# Mergen_Ground_Station_V2_0.net
KiCad netlist of a schematic drawn in EAGLE
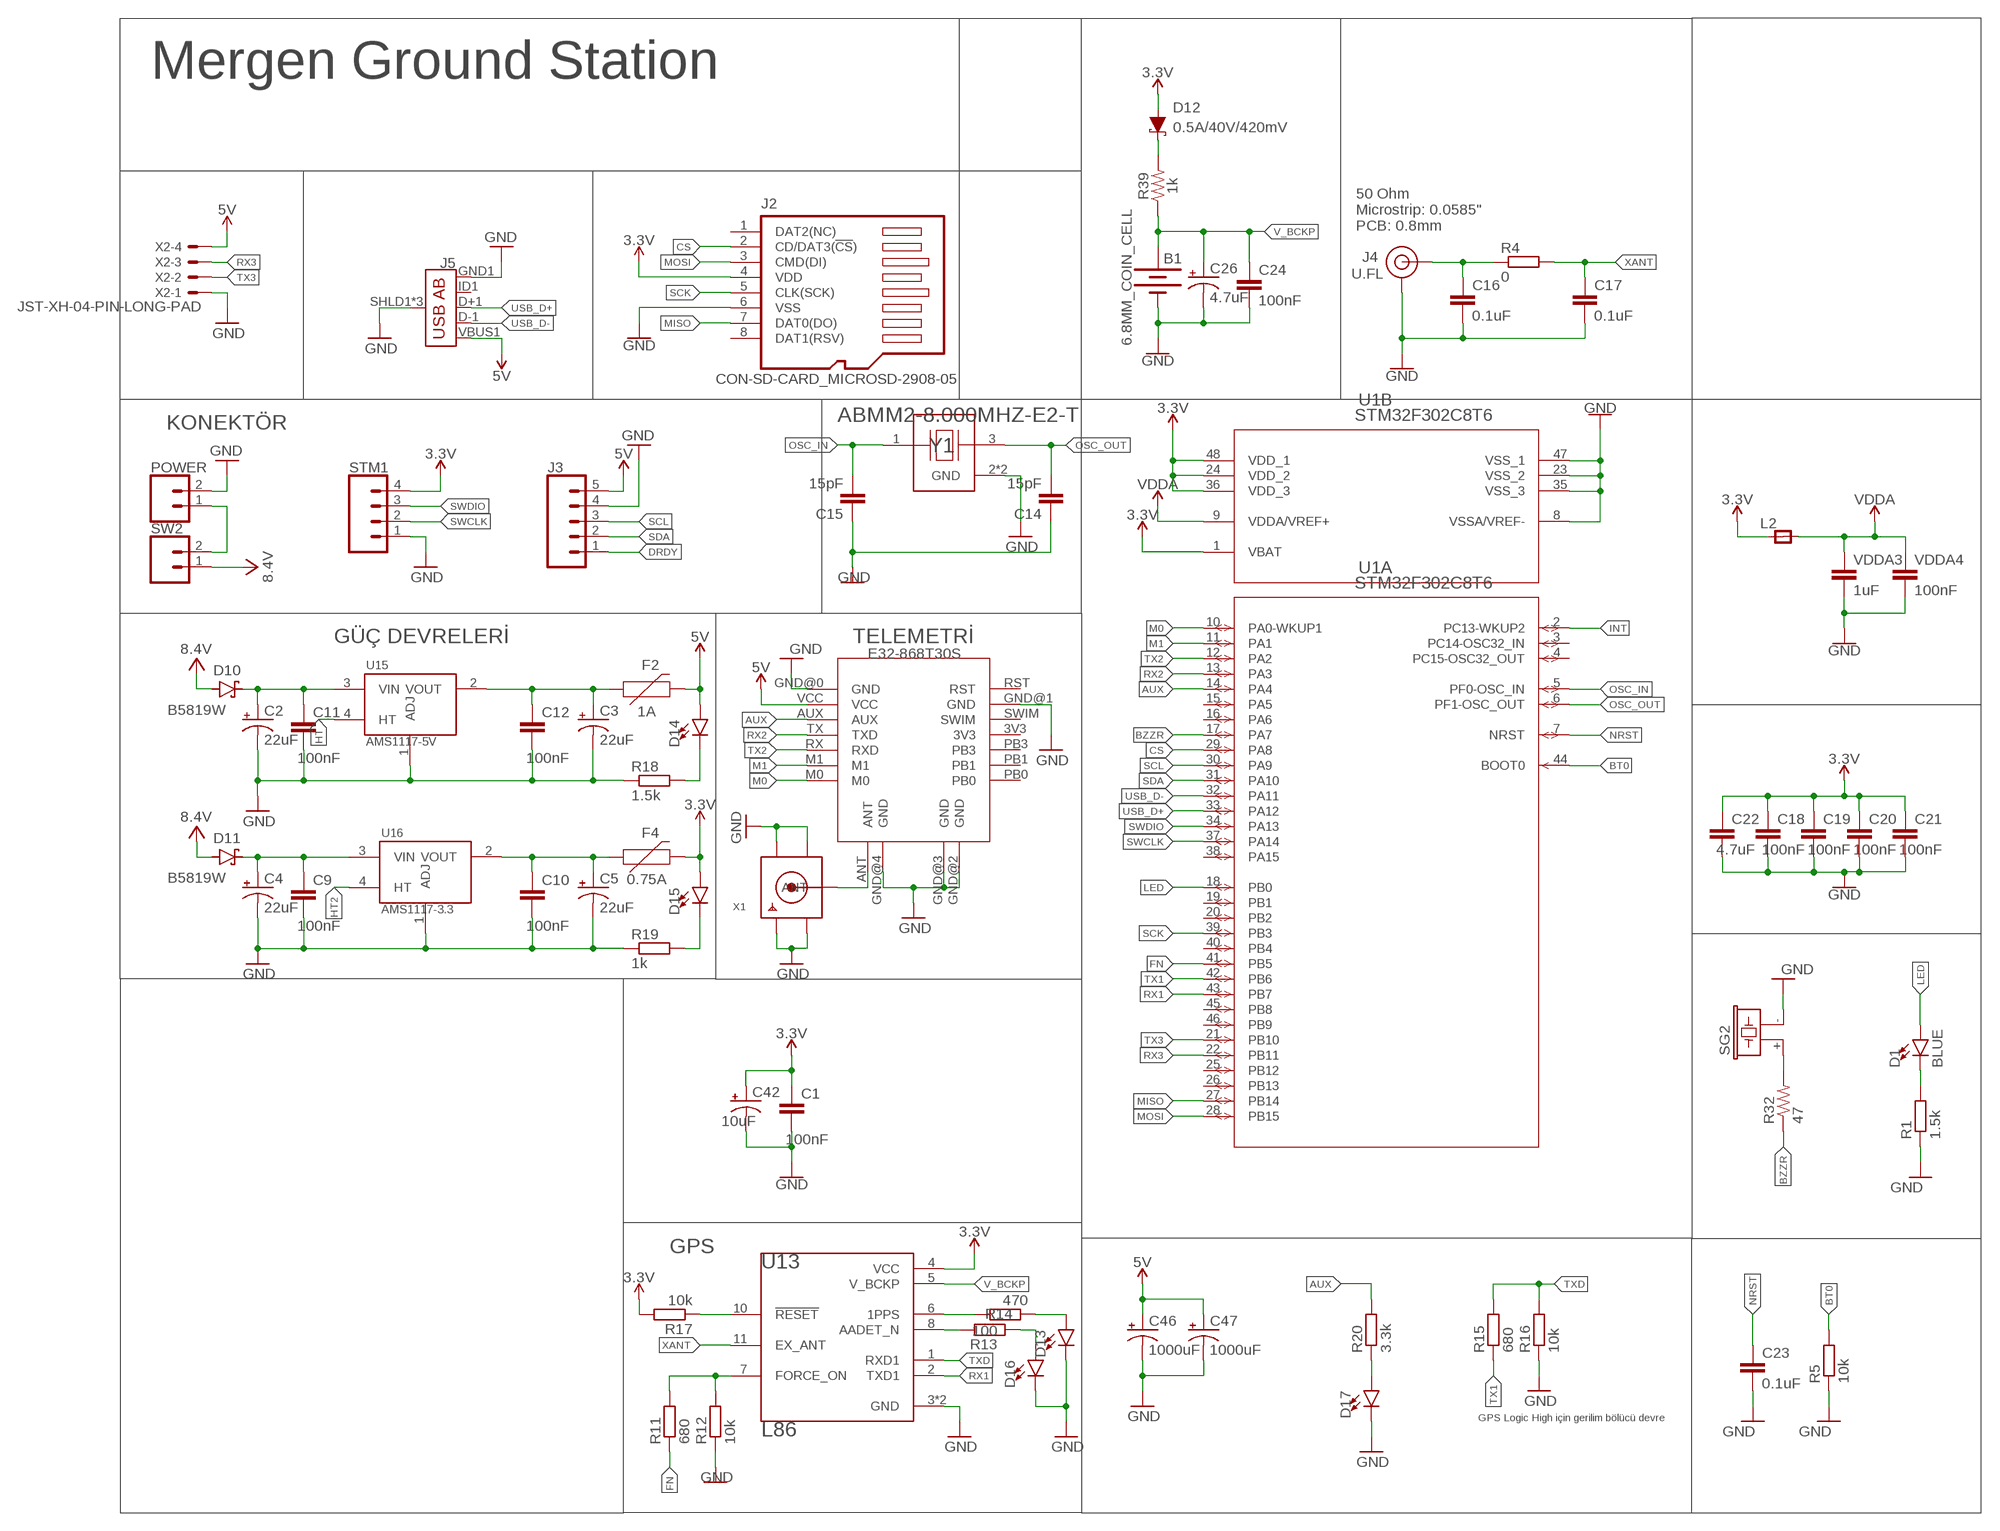
[diagram p0: schematic, sheet 1]

(export (version "E")
  (design (tool "Eeschema 10.0.6"))
  (components
    (comp (ref "B1")
      (value "6.8MM_COIN_CELL")
      (footprint "eagle-import:BATTCON-6.8MM")
      (libsource (lib "eagle-import") (part "BATTERY-6.8MM_SMD"))
    )
    (comp (ref "C1")
      (value "100nF")
      (footprint "eagle-import:C0603")
      (libsource (lib "eagle-import") (part "C-EUC0603"))
    )
    (comp (ref "C2")
      (value "22uF")
      (footprint "eagle-import:CT3528")
      (libsource (lib "eagle-import") (part "rcl_334_CPOL-USCT3528"))
    )
    (comp (ref "C3")
      (value "22uF")
      (footprint "eagle-import:CT3528")
      (libsource (lib "eagle-import") (part "rcl_334_CPOL-USCT3528"))
    )
    (comp (ref "C4")
      (value "22uF")
      (footprint "eagle-import:CT3528")
      (libsource (lib "eagle-import") (part "rcl_334_CPOL-USCT3528"))
    )
    (comp (ref "C5")
      (value "22uF")
      (footprint "eagle-import:CT3528")
      (libsource (lib "eagle-import") (part "rcl_334_CPOL-USCT3528"))
    )
    (comp (ref "C9")
      (value "100nF")
      (footprint "eagle-import:C0603")
      (libsource (lib "eagle-import") (part "C-EUC0603"))
    )
    (comp (ref "C10")
      (value "100nF")
      (footprint "eagle-import:C0603")
      (libsource (lib "eagle-import") (part "C-EUC0603"))
    )
    (comp (ref "C11")
      (value "100nF")
      (footprint "eagle-import:C0603")
      (libsource (lib "eagle-import") (part "C-EUC0603"))
    )
    (comp (ref "C12")
      (value "100nF")
      (footprint "eagle-import:C0603")
      (libsource (lib "eagle-import") (part "C-EUC0603"))
    )
    (comp (ref "C14")
      (value "15pF")
      (footprint "eagle-import:C0603")
      (libsource (lib "eagle-import") (part "C-EUC0603"))
    )
    (comp (ref "C15")
      (value "15pF")
      (footprint "eagle-import:C0603")
      (libsource (lib "eagle-import") (part "C-EUC0603"))
    )
    (comp (ref "C16")
      (value "0.1uF")
      (footprint "eagle-import:C0603")
      (libsource (lib "eagle-import") (part "C-EUC0603"))
    )
    (comp (ref "C17")
      (value "0.1uF")
      (footprint "eagle-import:C0603")
      (libsource (lib "eagle-import") (part "C-EUC0603"))
    )
    (comp (ref "C18")
      (value "100nF")
      (footprint "eagle-import:C0603")
      (libsource (lib "eagle-import") (part "C-EUC0603"))
    )
    (comp (ref "C19")
      (value "100nF")
      (footprint "eagle-import:C0603")
      (libsource (lib "eagle-import") (part "C-EUC0603"))
    )
    (comp (ref "C20")
      (value "100nF")
      (footprint "eagle-import:C0603")
      (libsource (lib "eagle-import") (part "C-EUC0603"))
    )
    (comp (ref "C21")
      (value "100nF")
      (footprint "eagle-import:C0603")
      (libsource (lib "eagle-import") (part "C-EUC0603"))
    )
    (comp (ref "C22")
      (value "4.7uF")
      (footprint "eagle-import:C0603")
      (libsource (lib "eagle-import") (part "C-EUC0603"))
    )
    (comp (ref "C23")
      (value "0.1uF")
      (footprint "eagle-import:C0603")
      (libsource (lib "eagle-import") (part "C-EUC0603"))
    )
    (comp (ref "C24")
      (value "100nF")
      (footprint "eagle-import:C0603")
      (libsource (lib "eagle-import") (part "C-EUC0603"))
    )
    (comp (ref "C26")
      (value "4.7uF")
      (footprint "eagle-import:A_3216-18R")
      (libsource (lib "eagle-import") (part "rcl_334_CPOL-USA/3216-18R"))
    )
    (comp (ref "C42")
      (value "10uF")
      (footprint "eagle-import:EIA3216")
      (libsource (lib "eagle-import") (part "10UF-POLAR-EIA3216-16V-10%(TANT)"))
    )
    (comp (ref "C46")
      (value "1000uF")
      (footprint "eagle-import:150CLZ-1010")
      (libsource (lib "eagle-import") (part "CPOL-US150CLZ-1010"))
    )
    (comp (ref "C47")
      (value "1000uF")
      (footprint "eagle-import:150CLZ-1010")
      (libsource (lib "eagle-import") (part "CPOL-US150CLZ-1010"))
    )
    (comp (ref "D1")
      (value "BLUE")
      (footprint "eagle-import:LED-0603")
      (libsource (lib "eagle-import") (part "LED0603"))
    )
    (comp (ref "D10")
      (value "B5819W")
      (footprint "eagle-import:SODFL3718X115")
      (fields (field (name "MANUFACTURER") "ON Semiconductor") (field (name "MPN") "MBR0520LT1G"))
      (libsource (lib "eagle-import") (part "SCHOTTKY_DO-219MBR0520LT1G"))
    )
    (comp (ref "D11")
      (value "B5819W")
      (footprint "eagle-import:SODFL3718X115")
      (fields (field (name "MANUFACTURER") "ON Semiconductor") (field (name "MPN") "MBR0520LT1G"))
      (libsource (lib "eagle-import") (part "SCHOTTKY_DO-219MBR0520LT1G"))
    )
    (comp (ref "D12")
      (value "0.5A/40V/420mV")
      (footprint "eagle-import:SOD-323")
      (libsource (lib "eagle-import") (part "DIODE-SCHOTTKY-PMEG4005EJ"))
    )
    (comp (ref "D13")
      (value "LED0603")
      (footprint "eagle-import:LED-0603")
      (libsource (lib "eagle-import") (part "LED0603"))
    )
    (comp (ref "D14")
      (value "LED0603")
      (footprint "eagle-import:LED-0603")
      (libsource (lib "eagle-import") (part "LED0603"))
    )
    (comp (ref "D15")
      (value "LED0603")
      (footprint "eagle-import:LED-0603")
      (libsource (lib "eagle-import") (part "LED0603"))
    )
    (comp (ref "D16")
      (value "LED0603")
      (footprint "eagle-import:LED-0603")
      (libsource (lib "eagle-import") (part "LED0603"))
    )
    (comp (ref "D17")
      (value "LED0603")
      (footprint "eagle-import:LED-0603")
      (libsource (lib "eagle-import") (part "LED0603"))
    )
    (comp (ref "F2")
      (value "1A")
      (footprint "eagle-import:1206")
      (libsource (lib "eagle-import") (part "PPTC_HALF-AMP"))
    )
    (comp (ref "F4")
      (value "0.75A")
      (footprint "eagle-import:1206")
      (libsource (lib "eagle-import") (part "PPTC_HALF-AMP"))
    )
    (comp (ref "J2")
      (value "CON-SD-CARD_MICROSD-2908-05")
      (footprint "eagle-import:CON-SD-CARD_2908-05")
      (libsource (lib "eagle-import") (part "CON-SD-CARD_MICROSD-2908-05"))
    )
    (comp (ref "J3")
      (value "CONN_05LOCK_LONGPADS")
      (footprint "eagle-import:1X05_LOCK_LONGPADS")
      (libsource (lib "eagle-import") (part "CONN_05LOCK_LONGPADS"))
    )
    (comp (ref "J4")
      (value "U.FL")
      (footprint "eagle-import:U.FL")
      (libsource (lib "eagle-import") (part "U.FL2PIN"))
    )
    (comp (ref "J5")
      (value "USB_AB_SMT")
      (footprint "eagle-import:USB-AB-MICRO-SMD")
      (libsource (lib "eagle-import") (part "USB_AB_SMT"))
    )
    (comp (ref "L2")
      (value "RC-MASTER-SMD_FB_0805MP")
      (footprint "eagle-import:RC-MASTER-SMD_L0805MP")
      (libsource (lib "eagle-import") (part "RC-MASTER-SMD_FB_0805MP"))
    )
    (comp (ref "POWER")
      (value "CONN_023.5MM-NO_SILK")
      (footprint "eagle-import:SCREWTERMINAL-3.5MM-2-NS")
      (libsource (lib "eagle-import") (part "CONN_023.5MM-NO_SILK"))
    )
    (comp (ref "R1")
      (value "1.5k")
      (footprint "eagle-import:R0603")
      (libsource (lib "eagle-import") (part "R-EU_R0603"))
    )
    (comp (ref "R4")
      (value "0")
      (footprint "eagle-import:R0603")
      (libsource (lib "eagle-import") (part "R-EU_R0603"))
    )
    (comp (ref "R5")
      (value "10k")
      (footprint "eagle-import:R0603")
      (libsource (lib "eagle-import") (part "R-EU_R0603"))
    )
    (comp (ref "R11")
      (value "680")
      (footprint "eagle-import:R0603")
      (libsource (lib "eagle-import") (part "R-EU_R0603"))
    )
    (comp (ref "R12")
      (value "10k")
      (footprint "eagle-import:R0603")
      (libsource (lib "eagle-import") (part "R-EU_R0603"))
    )
    (comp (ref "R13")
      (value "100")
      (footprint "eagle-import:R0603")
      (libsource (lib "eagle-import") (part "R-EU_R0603"))
    )
    (comp (ref "R14")
      (value "470")
      (footprint "eagle-import:R0603")
      (libsource (lib "eagle-import") (part "R-EU_R0603"))
    )
    (comp (ref "R15")
      (value "680")
      (footprint "eagle-import:R0603")
      (libsource (lib "eagle-import") (part "R-EU_R0603"))
    )
    (comp (ref "R16")
      (value "10k")
      (footprint "eagle-import:R0603")
      (libsource (lib "eagle-import") (part "R-EU_R0603"))
    )
    (comp (ref "R17")
      (value "10k")
      (footprint "eagle-import:R0603")
      (libsource (lib "eagle-import") (part "R-EU_R0603"))
    )
    (comp (ref "R18")
      (value "1.5k")
      (footprint "eagle-import:R0603")
      (libsource (lib "eagle-import") (part "R-EU_R0603"))
    )
    (comp (ref "R19")
      (value "1k")
      (footprint "eagle-import:R0603")
      (libsource (lib "eagle-import") (part "R-EU_R0603"))
    )
    (comp (ref "R20")
      (value "3.3k")
      (footprint "eagle-import:R0603")
      (libsource (lib "eagle-import") (part "R-EU_R0603"))
    )
    (comp (ref "R32")
      (value "47")
      (footprint "eagle-import:0603")
      (libsource (lib "eagle-import") (part "0OHM-0603-1/10W-5%"))
    )
    (comp (ref "R39")
      (value "1k")
      (footprint "eagle-import:0603")
      (libsource (lib "eagle-import") (part "1KOHM-0603-1/10W-1%"))
    )
    (comp (ref "SG2")
      (value "F/CM12P")
      (footprint "eagle-import:F_CM12P")
      (libsource (lib "eagle-import") (part "F/CM12P"))
    )
    (comp (ref "STM1")
      (value "CONN_04")
      (footprint "eagle-import:1X04")
      (libsource (lib "eagle-import") (part "CONN_04"))
    )
    (comp (ref "SW2")
      (value "CONN_023.5MM-NO_SILK")
      (footprint "eagle-import:SCREWTERMINAL-3.5MM-2-NS")
      (libsource (lib "eagle-import") (part "CONN_023.5MM-NO_SILK"))
    )
    (comp (ref "U1")
      (value "STM32F302C8T6")
      (footprint "eagle-import:LQFP48-7X7MM")
      (fields (field (name "COPYRIGHT") "Copyright (C) 2018 Accelerated Designs. All rights reserved"))
      (libsource (lib "eagle-import") (part "STM32F302C8T6"))
    )
    (comp (ref "U13")
      (value "L86")
      (footprint "eagle-import:XCVR_L86")
      (fields (field (name "MF") "Quectel"))
      (libsource (lib "eagle-import") (part "L86"))
    )
    (comp (ref "U14")
      (value "E32-868T30S")
      (footprint "eagle-import:E32-868T30S")
      (libsource (lib "eagle-import") (part "E32-868T30S"))
    )
    (comp (ref "U15")
      (value "AMS1117-5V")
      (footprint "eagle-import:SOT229P700X180-4N")
      (fields (field (name "MF") "Advanced Monolithic Systems") (field (name "MP") "AMS1117-3.3"))
      (libsource (lib "eagle-import") (part "AMS1117-3.3"))
    )
    (comp (ref "U16")
      (value "AMS1117-3.3")
      (footprint "eagle-import:SOT229P700X180-4N")
      (fields (field (name "MF") "Advanced Monolithic Systems"))
      (libsource (lib "eagle-import") (part "AMS1117-3.3"))
    )
    (comp (ref "VDDA3")
      (value "1uF")
      (footprint "eagle-import:0603")
      (libsource (lib "eagle-import") (part "0.1UF-0603-25V-(+80/-20%)"))
    )
    (comp (ref "VDDA4")
      (value "100nF")
      (footprint "eagle-import:0603")
      (libsource (lib "eagle-import") (part "0.1UF-0603-25V-(+80/-20%)"))
    )
    (comp (ref "X1")
      (value "SMACONNECTOR")
      (footprint "eagle-import:SMA90_DIP")
      (libsource (lib "eagle-import") (part "SMACONNECTOR"))
    )
    (comp (ref "X2")
      (value "JST-XH-04-PIN-LONG-PAD")
      (footprint "eagle-import:JST-XH-04-PACKAGE-LONG-PAD")
      (libsource (lib "eagle-import") (part "JST-XH-04-PIN-LONG-PAD"))
    )
    (comp (ref "Y1")
      (value "ABMM2-8.000MHZ-E2-T")
      (footprint "eagle-import:XTAL_ABMM2-8.000MHZ-E2-T")
      (fields (field (name "MF") "Abracon"))
      (libsource (lib "eagle-import") (part "ABMM2-8.000MHZ-E2-T"))
    )
  )
  (nets
    (net (code "1") (name "3.3V") (class "Default")
      (node (ref "C1") (pin "1") (pinfunction "1_1") (pintype "passive"))
      (node (ref "C18") (pin "1") (pinfunction "1_1") (pintype "passive"))
      (node (ref "C19") (pin "1") (pinfunction "1_1") (pintype "passive"))
      (node (ref "C20") (pin "1") (pinfunction "1_1") (pintype "passive"))
      (node (ref "C21") (pin "1") (pinfunction "1_1") (pintype "passive"))
      (node (ref "C22") (pin "1") (pinfunction "1_1") (pintype "passive"))
      (node (ref "C42") (pin "+") (pinfunction "+_+") (pintype "passive"))
      (node (ref "D12") (pin "A") (pinfunction "A_A") (pintype "passive"))
      (node (ref "D15") (pin "A") (pinfunction "A_A") (pintype "passive"))
      (node (ref "F4") (pin "2") (pinfunction "2_2") (pintype "bidirectional"))
      (node (ref "J2") (pin "4") (pinfunction "VDD_4") (pintype "bidirectional"))
      (node (ref "L2") (pin "1") (pinfunction "1_1") (pintype "passive"))
      (node (ref "R17") (pin "2") (pinfunction "2_2") (pintype "passive"))
      (node (ref "STM1") (pin "4") (pinfunction "4_4") (pintype "passive"))
      (node (ref "U1") (pin "1") (pinfunction "VBAT_1") (pintype "power_in"))
      (node (ref "U1") (pin "24") (pinfunction "VDD_2_24") (pintype "power_in"))
      (node (ref "U1") (pin "36") (pinfunction "VDD_3_36") (pintype "power_in"))
      (node (ref "U1") (pin "48") (pinfunction "VDD_1_48") (pintype "power_in"))
      (node (ref "U13") (pin "4") (pinfunction "VCC_4") (pintype "power_in"))
    )
    (net (code "2") (name "5V") (class "Default")
      (node (ref "C46") (pin "+") (pinfunction "+_+") (pintype "passive"))
      (node (ref "C47") (pin "+") (pinfunction "+_+") (pintype "passive"))
      (node (ref "D14") (pin "A") (pinfunction "A_A") (pintype "passive"))
      (node (ref "F2") (pin "2") (pinfunction "2_2") (pintype "bidirectional"))
      (node (ref "J3") (pin "5") (pinfunction "5_5") (pintype "passive"))
      (node (ref "J5") (pin "VBUS1") (pinfunction "VBUS_VBUS1") (pintype "power_in"))
      (node (ref "U14") (pin "VCC") (pinfunction "VCC_VCC") (pintype "bidirectional"))
      (node (ref "X2") (pin "4") (pinfunction "S_4") (pintype "passive"))
    )
    (net (code "3") (name "8.4V") (class "Default")
      (node (ref "D10") (pin "2") (pinfunction "A_2") (pintype "passive"))
      (node (ref "D11") (pin "2") (pinfunction "A_2") (pintype "passive"))
      (node (ref "SW2") (pin "1") (pinfunction "1_1") (pintype "passive"))
    )
    (net (code "4") (name "AUX") (class "Default")
      (node (ref "R20") (pin "2") (pinfunction "2_2") (pintype "passive"))
      (node (ref "U1") (pin "14") (pinfunction "PA4_14") (pintype "bidirectional"))
      (node (ref "U14") (pin "AUX") (pinfunction "AUX_AUX") (pintype "bidirectional"))
    )
    (net (code "5") (name "BT0") (class "Default")
      (node (ref "R5") (pin "2") (pinfunction "2_2") (pintype "passive"))
      (node (ref "U1") (pin "44") (pinfunction "BOOT0_44") (pintype "input"))
    )
    (net (code "6") (name "BZZR") (class "Default")
      (node (ref "R32") (pin "1") (pinfunction "1_1") (pintype "passive"))
      (node (ref "U1") (pin "17") (pinfunction "PA7_17") (pintype "bidirectional"))
    )
    (net (code "7") (name "CS") (class "Default")
      (node (ref "J2") (pin "2") (pinfunction "CD/DAT3(~{CS})_2") (pintype "bidirectional"))
      (node (ref "U1") (pin "29") (pinfunction "PA8_29") (pintype "bidirectional"))
    )
    (net (code "8") (name "DRDY") (class "Default")
      (node (ref "J3") (pin "1") (pinfunction "1_1") (pintype "passive"))
    )
    (net (code "9") (name "FN") (class "Default")
      (node (ref "R11") (pin "1") (pinfunction "1_1") (pintype "passive"))
      (node (ref "U1") (pin "41") (pinfunction "PB5_41") (pintype "bidirectional"))
    )
    (net (code "10") (name "GND") (class "Default")
      (node (ref "B1") (pin "-") (pinfunction "-_-") (pintype "power_in"))
      (node (ref "C1") (pin "2") (pinfunction "2_2") (pintype "passive"))
      (node (ref "C10") (pin "2") (pinfunction "2_2") (pintype "passive"))
      (node (ref "C11") (pin "2") (pinfunction "2_2") (pintype "passive"))
      (node (ref "C12") (pin "2") (pinfunction "2_2") (pintype "passive"))
      (node (ref "C14") (pin "1") (pinfunction "1_1") (pintype "passive"))
      (node (ref "C15") (pin "1") (pinfunction "1_1") (pintype "passive"))
      (node (ref "C16") (pin "2") (pinfunction "2_2") (pintype "passive"))
      (node (ref "C17") (pin "2") (pinfunction "2_2") (pintype "passive"))
      (node (ref "C18") (pin "2") (pinfunction "2_2") (pintype "passive"))
      (node (ref "C19") (pin "2") (pinfunction "2_2") (pintype "passive"))
      (node (ref "C2") (pin "-") (pinfunction "-_-") (pintype "passive"))
      (node (ref "C20") (pin "2") (pinfunction "2_2") (pintype "passive"))
      (node (ref "C21") (pin "2") (pinfunction "2_2") (pintype "passive"))
      (node (ref "C22") (pin "2") (pinfunction "2_2") (pintype "passive"))
      (node (ref "C23") (pin "2") (pinfunction "2_2") (pintype "passive"))
      (node (ref "C24") (pin "2") (pinfunction "2_2") (pintype "passive"))
      (node (ref "C26") (pin "-") (pinfunction "-_-") (pintype "passive"))
      (node (ref "C3") (pin "-") (pinfunction "-_-") (pintype "passive"))
      (node (ref "C4") (pin "-") (pinfunction "-_-") (pintype "passive"))
      (node (ref "C42") (pin "-") (pinfunction "-_-") (pintype "passive"))
      (node (ref "C46") (pin "-") (pinfunction "-_-") (pintype "passive"))
      (node (ref "C47") (pin "-") (pinfunction "-_-") (pintype "passive"))
      (node (ref "C5") (pin "-") (pinfunction "-_-") (pintype "passive"))
      (node (ref "C9") (pin "2") (pinfunction "2_2") (pintype "passive"))
      (node (ref "D13") (pin "C") (pinfunction "C_C") (pintype "passive"))
      (node (ref "D16") (pin "C") (pinfunction "C_C") (pintype "passive"))
      (node (ref "D17") (pin "C") (pinfunction "C_C") (pintype "passive"))
      (node (ref "J2") (pin "6") (pinfunction "VSS_6") (pintype "bidirectional"))
      (node (ref "J3") (pin "4") (pinfunction "4_4") (pintype "passive"))
      (node (ref "J4") (pin "1") (pinfunction "GND_1") (pintype "bidirectional"))
      (node (ref "J4") (pin "2") (pinfunction "GND_2") (pintype "bidirectional"))
      (node (ref "J5") (pin "GND1") (pinfunction "GND_GND1") (pintype "power_in"))
      (node (ref "J5") (pin "SHLD1") (pinfunction "SHIELD_SHLD1") (pintype "bidirectional"))
      (node (ref "J5") (pin "SHLD2") (pinfunction "SHIELD_SHLD2") (pintype "bidirectional"))
      (node (ref "J5") (pin "SHLD3") (pinfunction "SHIELD_SHLD3") (pintype "bidirectional"))
      (node (ref "POWER") (pin "2") (pinfunction "2_2") (pintype "passive"))
      (node (ref "R1") (pin "1") (pinfunction "1_1") (pintype "passive"))
      (node (ref "R12") (pin "1") (pinfunction "1_1") (pintype "passive"))
      (node (ref "R16") (pin "1") (pinfunction "1_1") (pintype "passive"))
      (node (ref "R18") (pin "1") (pinfunction "1_1") (pintype "passive"))
      (node (ref "R19") (pin "1") (pinfunction "1_1") (pintype "passive"))
      (node (ref "R5") (pin "1") (pinfunction "1_1") (pintype "passive"))
      (node (ref "SG2") (pin "-") (pinfunction "2_-") (pintype "passive"))
      (node (ref "STM1") (pin "1") (pinfunction "1_1") (pintype "passive"))
      (node (ref "U1") (pin "23") (pinfunction "VSS_2_23") (pintype "power_in"))
      (node (ref "U1") (pin "35") (pinfunction "VSS_3_35") (pintype "power_in"))
      (node (ref "U1") (pin "47") (pinfunction "VSS_1_47") (pintype "power_in"))
      (node (ref "U1") (pin "8") (pinfunction "VSSA/VREF-_8") (pintype "power_in"))
      (node (ref "U13") (pin "12") (pinfunction "GND_12") (pintype "passive"))
      (node (ref "U13") (pin "3") (pinfunction "GND_3") (pintype "passive"))
      (node (ref "U14") (pin "GND@0") (pinfunction "GND_GND@0") (pintype "bidirectional"))
      (node (ref "U14") (pin "GND@1") (pinfunction "GND_GND@1") (pintype "bidirectional"))
      (node (ref "U14") (pin "GND@2") (pinfunction "GND_GND@2") (pintype "bidirectional"))
      (node (ref "U14") (pin "GND@3") (pinfunction "GND_GND@3") (pintype "bidirectional"))
      (node (ref "U14") (pin "GND@4") (pinfunction "GND_GND@4") (pintype "bidirectional"))
      (node (ref "U15") (pin "1") (pinfunction "ADJ_1") (pintype "power_in"))
      (node (ref "U16") (pin "1") (pinfunction "ADJ_1") (pintype "power_in"))
      (node (ref "VDDA3") (pin "2") (pinfunction "2_2") (pintype "passive"))
      (node (ref "VDDA4") (pin "2") (pinfunction "2_2") (pintype "passive"))
      (node (ref "X1") (pin "GND1") (pinfunction "GND1_GND1") (pintype "power_in"))
      (node (ref "X1") (pin "GND2") (pinfunction "GND2_GND2") (pintype "power_in"))
      (node (ref "X1") (pin "GND3") (pinfunction "GND3_GND3") (pintype "power_in"))
      (node (ref "X1") (pin "GND4") (pinfunction "GND4_GND4") (pintype "power_in"))
      (node (ref "X2") (pin "1") (pinfunction "S_1") (pintype "passive"))
      (node (ref "Y1") (pin "2") (pinfunction "GND_2") (pintype "power_in"))
      (node (ref "Y1") (pin "4") (pinfunction "GND_4") (pintype "power_in"))
    )
    (net (code "11") (name "HT") (class "Default")
      (node (ref "U15") (pin "4") (pinfunction "HT_4") (pintype "bidirectional"))
    )
    (net (code "12") (name "HT2") (class "Default")
      (node (ref "U16") (pin "4") (pinfunction "HT_4") (pintype "bidirectional"))
    )
    (net (code "13") (name "INT") (class "Default")
      (node (ref "U1") (pin "2") (pinfunction "PC13-WKUP2_2") (pintype "bidirectional"))
    )
    (net (code "14") (name "LED") (class "Default")
      (node (ref "D1") (pin "A") (pinfunction "A_A") (pintype "passive"))
      (node (ref "U1") (pin "18") (pinfunction "PB0_18") (pintype "bidirectional"))
    )
    (net (code "15") (name "M0") (class "Default")
      (node (ref "U1") (pin "10") (pinfunction "PA0-WKUP1_10") (pintype "bidirectional"))
      (node (ref "U14") (pin "M0") (pinfunction "M0_M0") (pintype "bidirectional"))
    )
    (net (code "16") (name "M1") (class "Default")
      (node (ref "U1") (pin "11") (pinfunction "PA1_11") (pintype "bidirectional"))
      (node (ref "U14") (pin "M1") (pinfunction "M1_M1") (pintype "bidirectional"))
    )
    (net (code "17") (name "MISO") (class "Default")
      (node (ref "J2") (pin "7") (pinfunction "DAT0(DO)_7") (pintype "bidirectional"))
      (node (ref "U1") (pin "27") (pinfunction "PB14_27") (pintype "bidirectional"))
    )
    (net (code "18") (name "MOSI") (class "Default")
      (node (ref "J2") (pin "3") (pinfunction "CMD(DI)_3") (pintype "bidirectional"))
      (node (ref "U1") (pin "28") (pinfunction "PB15_28") (pintype "bidirectional"))
    )
    (net (code "19") (name "NRST") (class "Default")
      (node (ref "C23") (pin "1") (pinfunction "1_1") (pintype "passive"))
      (node (ref "U1") (pin "7") (pinfunction "NRST_7") (pintype "bidirectional"))
    )
    (net (code "20") (name "Net-(D1-PadC)") (class "Default")
      (node (ref "D1") (pin "C") (pinfunction "C_C") (pintype "passive"))
      (node (ref "R1") (pin "2") (pinfunction "2_2") (pintype "passive"))
    )
    (net (code "21") (name "Net-(D10-C)") (class "Default")
      (node (ref "C11") (pin "1") (pinfunction "1_1") (pintype "passive"))
      (node (ref "C2") (pin "+") (pinfunction "+_+") (pintype "passive"))
      (node (ref "D10") (pin "1") (pinfunction "C_1") (pintype "passive"))
      (node (ref "U15") (pin "3") (pinfunction "VIN_3") (pintype "input"))
    )
    (net (code "22") (name "Net-(D11-C)") (class "Default")
      (node (ref "C4") (pin "+") (pinfunction "+_+") (pintype "passive"))
      (node (ref "C9") (pin "1") (pinfunction "1_1") (pintype "passive"))
      (node (ref "D11") (pin "1") (pinfunction "C_1") (pintype "passive"))
      (node (ref "U16") (pin "3") (pinfunction "VIN_3") (pintype "input"))
    )
    (net (code "23") (name "Net-(D12-PadC)") (class "Default")
      (node (ref "D12") (pin "C") (pinfunction "C_C") (pintype "passive"))
      (node (ref "R39") (pin "2") (pinfunction "2_2") (pintype "passive"))
    )
    (net (code "24") (name "Net-(D13-PadA)") (class "Default")
      (node (ref "D13") (pin "A") (pinfunction "A_A") (pintype "passive"))
      (node (ref "R14") (pin "1") (pinfunction "1_1") (pintype "passive"))
    )
    (net (code "25") (name "Net-(D14-PadC)") (class "Default")
      (node (ref "D14") (pin "C") (pinfunction "C_C") (pintype "passive"))
      (node (ref "R18") (pin "2") (pinfunction "2_2") (pintype "passive"))
    )
    (net (code "26") (name "Net-(D15-PadC)") (class "Default")
      (node (ref "D15") (pin "C") (pinfunction "C_C") (pintype "passive"))
      (node (ref "R19") (pin "2") (pinfunction "2_2") (pintype "passive"))
    )
    (net (code "27") (name "Net-(D16-PadA)") (class "Default")
      (node (ref "D16") (pin "A") (pinfunction "A_A") (pintype "passive"))
      (node (ref "R13") (pin "1") (pinfunction "1_1") (pintype "passive"))
    )
    (net (code "28") (name "Net-(D17-PadA)") (class "Default")
      (node (ref "D17") (pin "A") (pinfunction "A_A") (pintype "passive"))
      (node (ref "R20") (pin "1") (pinfunction "1_1") (pintype "passive"))
    )
    (net (code "29") (name "Net-(J4-SIGNAL)") (class "Default")
      (node (ref "C16") (pin "1") (pinfunction "1_1") (pintype "passive"))
      (node (ref "J4") (pin "FEED") (pinfunction "SIGNAL_FEED") (pintype "bidirectional"))
      (node (ref "R4") (pin "1") (pinfunction "1_1") (pintype "passive"))
    )
    (net (code "30") (name "Net-(POWER-Pad1)") (class "Default")
      (node (ref "POWER") (pin "1") (pinfunction "1_1") (pintype "passive"))
      (node (ref "SW2") (pin "2") (pinfunction "2_2") (pintype "passive"))
    )
    (net (code "31") (name "Net-(SG2-1)") (class "Default")
      (node (ref "R32") (pin "2") (pinfunction "2_2") (pintype "passive"))
      (node (ref "SG2") (pin "+") (pinfunction "1_+") (pintype "passive"))
    )
    (net (code "32") (name "Net-(U13-1PPS)") (class "Default")
      (node (ref "R14") (pin "2") (pinfunction "2_2") (pintype "passive"))
      (node (ref "U13") (pin "6") (pinfunction "1PPS_6") (pintype "output"))
    )
    (net (code "33") (name "Net-(U13-AADET_N)") (class "Default")
      (node (ref "R13") (pin "2") (pinfunction "2_2") (pintype "passive"))
      (node (ref "U13") (pin "8") (pinfunction "AADET_N_8") (pintype "output"))
    )
    (net (code "34") (name "Net-(U13-FORCE_ON)") (class "Default")
      (node (ref "R11") (pin "2") (pinfunction "2_2") (pintype "passive"))
      (node (ref "R12") (pin "2") (pinfunction "2_2") (pintype "passive"))
      (node (ref "U13") (pin "7") (pinfunction "FORCE_ON_7") (pintype "input"))
    )
    (net (code "35") (name "Net-(U13-~{RESET})") (class "Default")
      (node (ref "R17") (pin "1") (pinfunction "1_1") (pintype "passive"))
      (node (ref "U13") (pin "10") (pinfunction "~{RESET}_10") (pintype "input"))
    )
    (net (code "36") (name "Net-(U15-VOUT)") (class "Default")
      (node (ref "C12") (pin "1") (pinfunction "1_1") (pintype "passive"))
      (node (ref "C3") (pin "+") (pinfunction "+_+") (pintype "passive"))
      (node (ref "F2") (pin "1") (pinfunction "1_1") (pintype "bidirectional"))
      (node (ref "U15") (pin "2") (pinfunction "VOUT_2") (pintype "output"))
    )
    (net (code "37") (name "Net-(U16-VOUT)") (class "Default")
      (node (ref "C10") (pin "1") (pinfunction "1_1") (pintype "passive"))
      (node (ref "C5") (pin "+") (pinfunction "+_+") (pintype "passive"))
      (node (ref "F4") (pin "1") (pinfunction "1_1") (pintype "bidirectional"))
      (node (ref "U16") (pin "2") (pinfunction "VOUT_2") (pintype "output"))
    )
    (net (code "38") (name "Net-(X1-ANT)") (class "Default")
      (node (ref "U14") (pin "ANT") (pinfunction "ANT_ANT") (pintype "bidirectional"))
      (node (ref "X1") (pin "ANTENNA") (pinfunction "ANT_ANTENNA") (pintype "bidirectional"))
    )
    (net (code "39") (name "OSC_IN") (class "Default")
      (node (ref "C15") (pin "2") (pinfunction "2_2") (pintype "passive"))
      (node (ref "U1") (pin "5") (pinfunction "PF0-OSC_IN_5") (pintype "bidirectional"))
      (node (ref "Y1") (pin "1") (pinfunction "1_1") (pintype "passive"))
    )
    (net (code "40") (name "OSC_OUT") (class "Default")
      (node (ref "C14") (pin "2") (pinfunction "2_2") (pintype "passive"))
      (node (ref "U1") (pin "6") (pinfunction "PF1-OSC_OUT_6") (pintype "bidirectional"))
      (node (ref "Y1") (pin "3") (pinfunction "3_3") (pintype "passive"))
    )
    (net (code "41") (name "RX1") (class "Default")
      (node (ref "U1") (pin "43") (pinfunction "PB7_43") (pintype "bidirectional"))
      (node (ref "U13") (pin "2") (pinfunction "TXD1_2") (pintype "output"))
    )
    (net (code "42") (name "RX2") (class "Default")
      (node (ref "U1") (pin "13") (pinfunction "PA3_13") (pintype "bidirectional"))
      (node (ref "U14") (pin "TX") (pinfunction "TXD_TX") (pintype "bidirectional"))
    )
    (net (code "43") (name "RX3") (class "Default")
      (node (ref "U1") (pin "22") (pinfunction "PB11_22") (pintype "bidirectional"))
      (node (ref "X2") (pin "3") (pinfunction "S_3") (pintype "passive"))
    )
    (net (code "44") (name "SCK") (class "Default")
      (node (ref "J2") (pin "5") (pinfunction "CLK(SCK)_5") (pintype "bidirectional"))
      (node (ref "U1") (pin "39") (pinfunction "PB3_39") (pintype "bidirectional"))
    )
    (net (code "45") (name "SCL") (class "Default")
      (node (ref "J3") (pin "3") (pinfunction "3_3") (pintype "passive"))
      (node (ref "U1") (pin "30") (pinfunction "PA9_30") (pintype "bidirectional"))
    )
    (net (code "46") (name "SDA") (class "Default")
      (node (ref "J3") (pin "2") (pinfunction "2_2") (pintype "passive"))
      (node (ref "U1") (pin "31") (pinfunction "PA10_31") (pintype "bidirectional"))
    )
    (net (code "47") (name "SWCLK") (class "Default")
      (node (ref "STM1") (pin "2") (pinfunction "2_2") (pintype "passive"))
      (node (ref "U1") (pin "37") (pinfunction "PA14_37") (pintype "bidirectional"))
    )
    (net (code "48") (name "SWDIO") (class "Default")
      (node (ref "STM1") (pin "3") (pinfunction "3_3") (pintype "passive"))
      (node (ref "U1") (pin "34") (pinfunction "PA13_34") (pintype "bidirectional"))
    )
    (net (code "49") (name "TX1") (class "Default")
      (node (ref "R15") (pin "1") (pinfunction "1_1") (pintype "passive"))
      (node (ref "U1") (pin "42") (pinfunction "PB6_42") (pintype "bidirectional"))
    )
    (net (code "50") (name "TX2") (class "Default")
      (node (ref "U1") (pin "12") (pinfunction "PA2_12") (pintype "bidirectional"))
      (node (ref "U14") (pin "RX") (pinfunction "RXD_RX") (pintype "bidirectional"))
    )
    (net (code "51") (name "TX3") (class "Default")
      (node (ref "U1") (pin "21") (pinfunction "PB10_21") (pintype "bidirectional"))
      (node (ref "X2") (pin "2") (pinfunction "S_2") (pintype "passive"))
    )
    (net (code "52") (name "TXD") (class "Default")
      (node (ref "R15") (pin "2") (pinfunction "2_2") (pintype "passive"))
      (node (ref "R16") (pin "2") (pinfunction "2_2") (pintype "passive"))
      (node (ref "U13") (pin "1") (pinfunction "RXD1_1") (pintype "input"))
    )
    (net (code "53") (name "USB_D+") (class "Default")
      (node (ref "J5") (pin "D+1") (pinfunction "D+_D+1") (pintype "bidirectional"))
      (node (ref "U1") (pin "33") (pinfunction "PA12_33") (pintype "bidirectional"))
    )
    (net (code "54") (name "USB_D-") (class "Default")
      (node (ref "J5") (pin "D-1") (pinfunction "D-_D-1") (pintype "bidirectional"))
      (node (ref "U1") (pin "32") (pinfunction "PA11_32") (pintype "bidirectional"))
    )
    (net (code "55") (name "VDDA") (class "Default")
      (node (ref "L2") (pin "2") (pinfunction "2_2") (pintype "passive"))
      (node (ref "U1") (pin "9") (pinfunction "VDDA/VREF+_9") (pintype "power_in"))
      (node (ref "VDDA3") (pin "1") (pinfunction "1_1") (pintype "passive"))
      (node (ref "VDDA4") (pin "1") (pinfunction "1_1") (pintype "passive"))
    )
    (net (code "56") (name "V_BCKP") (class "Default")
      (node (ref "B1") (pin "+") (pinfunction "+_+") (pintype "power_in"))
      (node (ref "C24") (pin "1") (pinfunction "1_1") (pintype "passive"))
      (node (ref "C26") (pin "+") (pinfunction "+_+") (pintype "passive"))
      (node (ref "R39") (pin "1") (pinfunction "1_1") (pintype "passive"))
      (node (ref "U13") (pin "5") (pinfunction "V_BCKP_5") (pintype "power_in"))
    )
    (net (code "57") (name "XANT") (class "Default")
      (node (ref "C17") (pin "1") (pinfunction "1_1") (pintype "passive"))
      (node (ref "R4") (pin "2") (pinfunction "2_2") (pintype "passive"))
      (node (ref "U13") (pin "11") (pinfunction "EX_ANT_11") (pintype "input"))
    )
    (net (code "58") (name "unconnected-(J2B-DAT1(RSV)-Pad8)") (class "Default")
      (node (ref "J2") (pin "8") (pinfunction "DAT1(RSV)_8") (pintype "bidirectional"))
    )
    (net (code "59") (name "unconnected-(J2B-DAT2(NC)-Pad1)") (class "Default")
      (node (ref "J2") (pin "1") (pinfunction "DAT2(NC)_1") (pintype "bidirectional"))
    )
    (net (code "60") (name "unconnected-(J5-USBID-PadID1)") (class "Default")
      (node (ref "J5") (pin "ID1") (pinfunction "USBID_ID1") (pintype "bidirectional"))
    )
    (net (code "61") (name "unconnected-(U1A-PA5-Pad15)") (class "Default")
      (node (ref "U1") (pin "15") (pinfunction "PA5_15") (pintype "bidirectional"))
    )
    (net (code "62") (name "unconnected-(U1A-PA6-Pad16)") (class "Default")
      (node (ref "U1") (pin "16") (pinfunction "PA6_16") (pintype "bidirectional"))
    )
    (net (code "63") (name "unconnected-(U1A-PA15-Pad38)") (class "Default")
      (node (ref "U1") (pin "38") (pinfunction "PA15_38") (pintype "bidirectional"))
    )
    (net (code "64") (name "unconnected-(U1A-PB1-Pad19)") (class "Default")
      (node (ref "U1") (pin "19") (pinfunction "PB1_19") (pintype "bidirectional"))
    )
    (net (code "65") (name "unconnected-(U1A-PB2-Pad20)") (class "Default")
      (node (ref "U1") (pin "20") (pinfunction "PB2_20") (pintype "bidirectional"))
    )
    (net (code "66") (name "unconnected-(U1A-PB4-Pad40)") (class "Default")
      (node (ref "U1") (pin "40") (pinfunction "PB4_40") (pintype "bidirectional"))
    )
    (net (code "67") (name "unconnected-(U1A-PB8-Pad45)") (class "Default")
      (node (ref "U1") (pin "45") (pinfunction "PB8_45") (pintype "bidirectional"))
    )
    (net (code "68") (name "unconnected-(U1A-PB9-Pad46)") (class "Default")
      (node (ref "U1") (pin "46") (pinfunction "PB9_46") (pintype "bidirectional"))
    )
    (net (code "69") (name "unconnected-(U1A-PB12-Pad25)") (class "Default")
      (node (ref "U1") (pin "25") (pinfunction "PB12_25") (pintype "bidirectional"))
    )
    (net (code "70") (name "unconnected-(U1A-PB13-Pad26)") (class "Default")
      (node (ref "U1") (pin "26") (pinfunction "PB13_26") (pintype "bidirectional"))
    )
    (net (code "71") (name "unconnected-(U1A-PC14-OSC32_IN-Pad3)") (class "Default")
      (node (ref "U1") (pin "3") (pinfunction "PC14-OSC32_IN_3") (pintype "bidirectional"))
    )
    (net (code "72") (name "unconnected-(U1A-PC15-OSC32_OUT-Pad4)") (class "Default")
      (node (ref "U1") (pin "4") (pinfunction "PC15-OSC32_OUT_4") (pintype "bidirectional"))
    )
    (net (code "73") (name "unconnected-(U14-Pad3V3)") (class "Default")
      (node (ref "U14") (pin "3V3") (pinfunction "3V3_3V3") (pintype "bidirectional"))
    )
    (net (code "74") (name "unconnected-(U14-PadPB0)") (class "Default")
      (node (ref "U14") (pin "PB0") (pinfunction "PB0_PB0") (pintype "bidirectional"))
    )
    (net (code "75") (name "unconnected-(U14-PadPB1)") (class "Default")
      (node (ref "U14") (pin "PB1") (pinfunction "PB1_PB1") (pintype "bidirectional"))
    )
    (net (code "76") (name "unconnected-(U14-PadPB3)") (class "Default")
      (node (ref "U14") (pin "PB3") (pinfunction "PB3_PB3") (pintype "bidirectional"))
    )
    (net (code "77") (name "unconnected-(U14-PadRST)") (class "Default")
      (node (ref "U14") (pin "RST") (pinfunction "RST_RST") (pintype "bidirectional"))
    )
    (net (code "78") (name "unconnected-(U14-PadSWIM)") (class "Default")
      (node (ref "U14") (pin "SWIM") (pinfunction "SWIM_SWIM") (pintype "bidirectional"))
    )
  )
)
